# ch340g.net
KiCad netlist of a schematic drawn in EAGLE
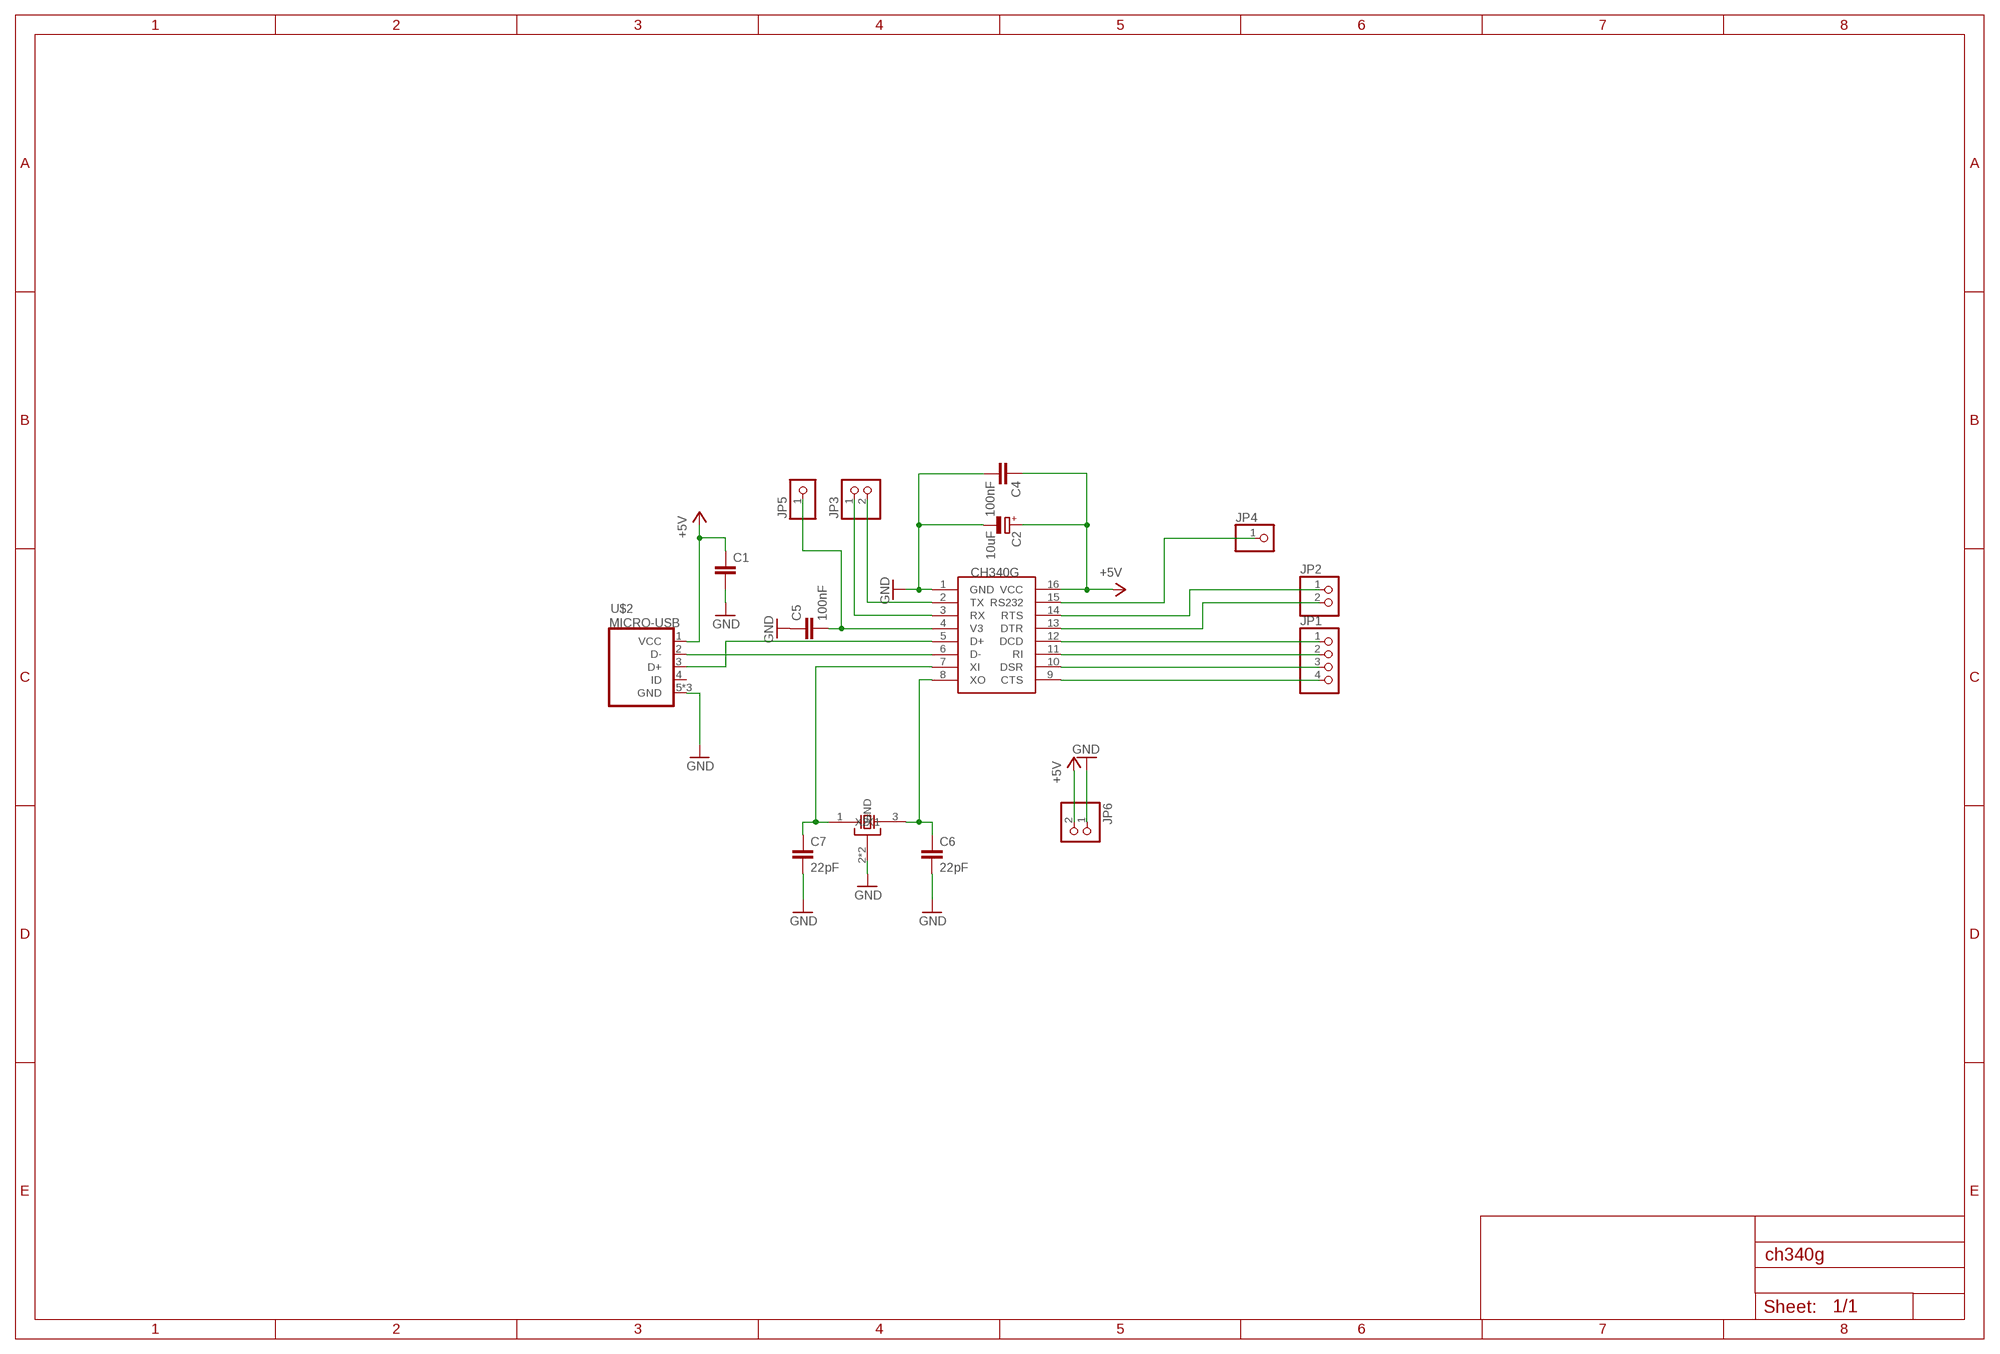
[diagram p0: schematic, sheet 1]

(export (version "E")
  (design (tool "Eeschema 10.0.6"))
  (components
    (comp (ref "C1")
      (value "C-EUC1206K")
      (footprint "eagle-import:C1206K")
      (libsource (lib "eagle-import") (part "C-EUC1206K"))
    )
    (comp (ref "C2")
      (value "10uF")
      (footprint "eagle-import:SMC_A")
      (libsource (lib "eagle-import") (part "CPOL-EUSMCA"))
    )
    (comp (ref "C4")
      (value "100nF")
      (footprint "eagle-import:C0805")
      (libsource (lib "eagle-import") (part "C-EUC0805"))
    )
    (comp (ref "C5")
      (value "100nF")
      (footprint "eagle-import:C1206K")
      (libsource (lib "eagle-import") (part "C-EUC1206K"))
    )
    (comp (ref "C6")
      (value "22pF")
      (footprint "eagle-import:C0805")
      (libsource (lib "eagle-import") (part "C-EUC0805"))
    )
    (comp (ref "C7")
      (value "22pF")
      (footprint "eagle-import:C0805")
      (libsource (lib "eagle-import") (part "C-EUC0805"))
    )
    (comp (ref "JP1")
      (value "PINHD-1X4")
      (footprint "eagle-import:1X04")
      (libsource (lib "eagle-import") (part "PINHD-1X4"))
    )
    (comp (ref "JP2")
      (value "PINHD-1X2")
      (footprint "eagle-import:1X02")
      (libsource (lib "eagle-import") (part "PINHD-1X2"))
    )
    (comp (ref "JP3")
      (value "PINHD-1X2")
      (footprint "eagle-import:1X02")
      (libsource (lib "eagle-import") (part "PINHD-1X2"))
    )
    (comp (ref "JP4")
      (value "PINHD-1X1")
      (footprint "eagle-import:1X01")
      (libsource (lib "eagle-import") (part "PINHD-1X1"))
    )
    (comp (ref "JP5")
      (value "PINHD-1X1")
      (footprint "eagle-import:1X01")
      (libsource (lib "eagle-import") (part "PINHD-1X1"))
    )
    (comp (ref "JP6")
      (value "PINHD-1X2")
      (footprint "eagle-import:1X02")
      (libsource (lib "eagle-import") (part "PINHD-1X2"))
    )
    (comp (ref "U$1")
      (value "CH340G")
      (footprint "eagle-import:SOIC16")
      (libsource (lib "eagle-import") (part "CH340G"))
    )
    (comp (ref "U$2")
      (value "MICRO-USB")
      (footprint "eagle-import:MICRO-USB")
      (libsource (lib "eagle-import") (part "MICRO-USB"))
    )
    (comp (ref "U$3")
      (value "CTS_32X25_SMD")
      (footprint "eagle-import:CTS_32X25")
      (libsource (lib "eagle-import") (part "CTS_32X25_SMD"))
    )
  )
  (nets
    (net (code "1") (name "+5V") (class "Default")
      (node (ref "C1") (pin "1") (pinfunction "1_1") (pintype "passive"))
      (node (ref "C2") (pin "+") (pinfunction "+_+") (pintype "passive"))
      (node (ref "C4") (pin "1") (pinfunction "1_1") (pintype "passive"))
      (node (ref "JP6") (pin "2") (pinfunction "2_2") (pintype "passive"))
      (node (ref "U$1") (pin "16") (pinfunction "VCC_16") (pintype "bidirectional"))
      (node (ref "U$2") (pin "1") (pinfunction "VCC_1") (pintype "power_in"))
    )
    (net (code "2") (name "GND") (class "Default")
      (node (ref "C1") (pin "2") (pinfunction "2_2") (pintype "passive"))
      (node (ref "C2") (pin "-") (pinfunction "-_-") (pintype "passive"))
      (node (ref "C4") (pin "2") (pinfunction "2_2") (pintype "passive"))
      (node (ref "C5") (pin "1") (pinfunction "1_1") (pintype "passive"))
      (node (ref "C6") (pin "2") (pinfunction "2_2") (pintype "passive"))
      (node (ref "C7") (pin "2") (pinfunction "2_2") (pintype "passive"))
      (node (ref "JP6") (pin "1") (pinfunction "1_1") (pintype "passive"))
      (node (ref "U$1") (pin "1") (pinfunction "GND_1") (pintype "bidirectional"))
      (node (ref "U$2") (pin "5") (pinfunction "GND_5") (pintype "power_in"))
      (node (ref "U$2") (pin "GND1") (pinfunction "GND_GND1") (pintype "power_in"))
      (node (ref "U$2") (pin "GND2") (pinfunction "GND_GND2") (pintype "power_in"))
      (node (ref "U$3") (pin "2") (pinfunction "GND_2") (pintype "power_in"))
      (node (ref "U$3") (pin "4") (pinfunction "GND_4") (pintype "power_in"))
    )
    (net (code "3") (name "Net-(U$1-CTS)") (class "Default")
      (node (ref "JP1") (pin "4") (pinfunction "4_4") (pintype "passive"))
      (node (ref "U$1") (pin "9") (pinfunction "CTS_9") (pintype "bidirectional"))
    )
    (net (code "4") (name "Net-(U$1-D+)") (class "Default")
      (node (ref "U$1") (pin "5") (pinfunction "D+_5") (pintype "bidirectional"))
      (node (ref "U$2") (pin "3") (pinfunction "D+_3") (pintype "bidirectional"))
    )
    (net (code "5") (name "Net-(U$1-D-)") (class "Default")
      (node (ref "U$1") (pin "6") (pinfunction "D-_6") (pintype "bidirectional"))
      (node (ref "U$2") (pin "2") (pinfunction "D-_2") (pintype "bidirectional"))
    )
    (net (code "6") (name "Net-(U$1-DCD)") (class "Default")
      (node (ref "JP1") (pin "1") (pinfunction "1_1") (pintype "passive"))
      (node (ref "U$1") (pin "12") (pinfunction "DCD_12") (pintype "bidirectional"))
    )
    (net (code "7") (name "Net-(U$1-DSR)") (class "Default")
      (node (ref "JP1") (pin "3") (pinfunction "3_3") (pintype "passive"))
      (node (ref "U$1") (pin "10") (pinfunction "DSR_10") (pintype "bidirectional"))
    )
    (net (code "8") (name "Net-(U$1-DTR)") (class "Default")
      (node (ref "JP2") (pin "2") (pinfunction "2_2") (pintype "passive"))
      (node (ref "U$1") (pin "13") (pinfunction "DTR_13") (pintype "bidirectional"))
    )
    (net (code "9") (name "Net-(U$1-RI)") (class "Default")
      (node (ref "JP1") (pin "2") (pinfunction "2_2") (pintype "passive"))
      (node (ref "U$1") (pin "11") (pinfunction "RI_11") (pintype "bidirectional"))
    )
    (net (code "10") (name "Net-(U$1-RS232)") (class "Default")
      (node (ref "JP4") (pin "1") (pinfunction "1_1") (pintype "passive"))
      (node (ref "U$1") (pin "15") (pinfunction "RS232_15") (pintype "bidirectional"))
    )
    (net (code "11") (name "Net-(U$1-RTS)") (class "Default")
      (node (ref "JP2") (pin "1") (pinfunction "1_1") (pintype "passive"))
      (node (ref "U$1") (pin "14") (pinfunction "RTS_14") (pintype "bidirectional"))
    )
    (net (code "12") (name "Net-(U$1-RX)") (class "Default")
      (node (ref "JP3") (pin "1") (pinfunction "1_1") (pintype "passive"))
      (node (ref "U$1") (pin "3") (pinfunction "RX_3") (pintype "bidirectional"))
    )
    (net (code "13") (name "Net-(U$1-TX)") (class "Default")
      (node (ref "JP3") (pin "2") (pinfunction "2_2") (pintype "passive"))
      (node (ref "U$1") (pin "2") (pinfunction "TX_2") (pintype "bidirectional"))
    )
    (net (code "14") (name "Net-(U$1-V3)") (class "Default")
      (node (ref "C5") (pin "2") (pinfunction "2_2") (pintype "passive"))
      (node (ref "JP5") (pin "1") (pinfunction "1_1") (pintype "passive"))
      (node (ref "U$1") (pin "4") (pinfunction "V3_4") (pintype "bidirectional"))
    )
    (net (code "15") (name "Net-(U$1-XI)") (class "Default")
      (node (ref "C7") (pin "1") (pinfunction "1_1") (pintype "passive"))
      (node (ref "U$1") (pin "7") (pinfunction "XI_7") (pintype "bidirectional"))
      (node (ref "U$3") (pin "1") (pinfunction "X1_1") (pintype "bidirectional"))
    )
    (net (code "16") (name "Net-(U$1-XO)") (class "Default")
      (node (ref "C6") (pin "1") (pinfunction "1_1") (pintype "passive"))
      (node (ref "U$1") (pin "8") (pinfunction "XO_8") (pintype "bidirectional"))
      (node (ref "U$3") (pin "3") (pinfunction "X2_3") (pintype "bidirectional"))
    )
    (net (code "17") (name "unconnected-(U$2-ID-Pad4)") (class "Default")
      (node (ref "U$2") (pin "4") (pinfunction "ID_4") (pintype "bidirectional"))
    )
  )
)
